# Rectification_filter.net
KiCad netlist of a schematic drawn in Altium Designer
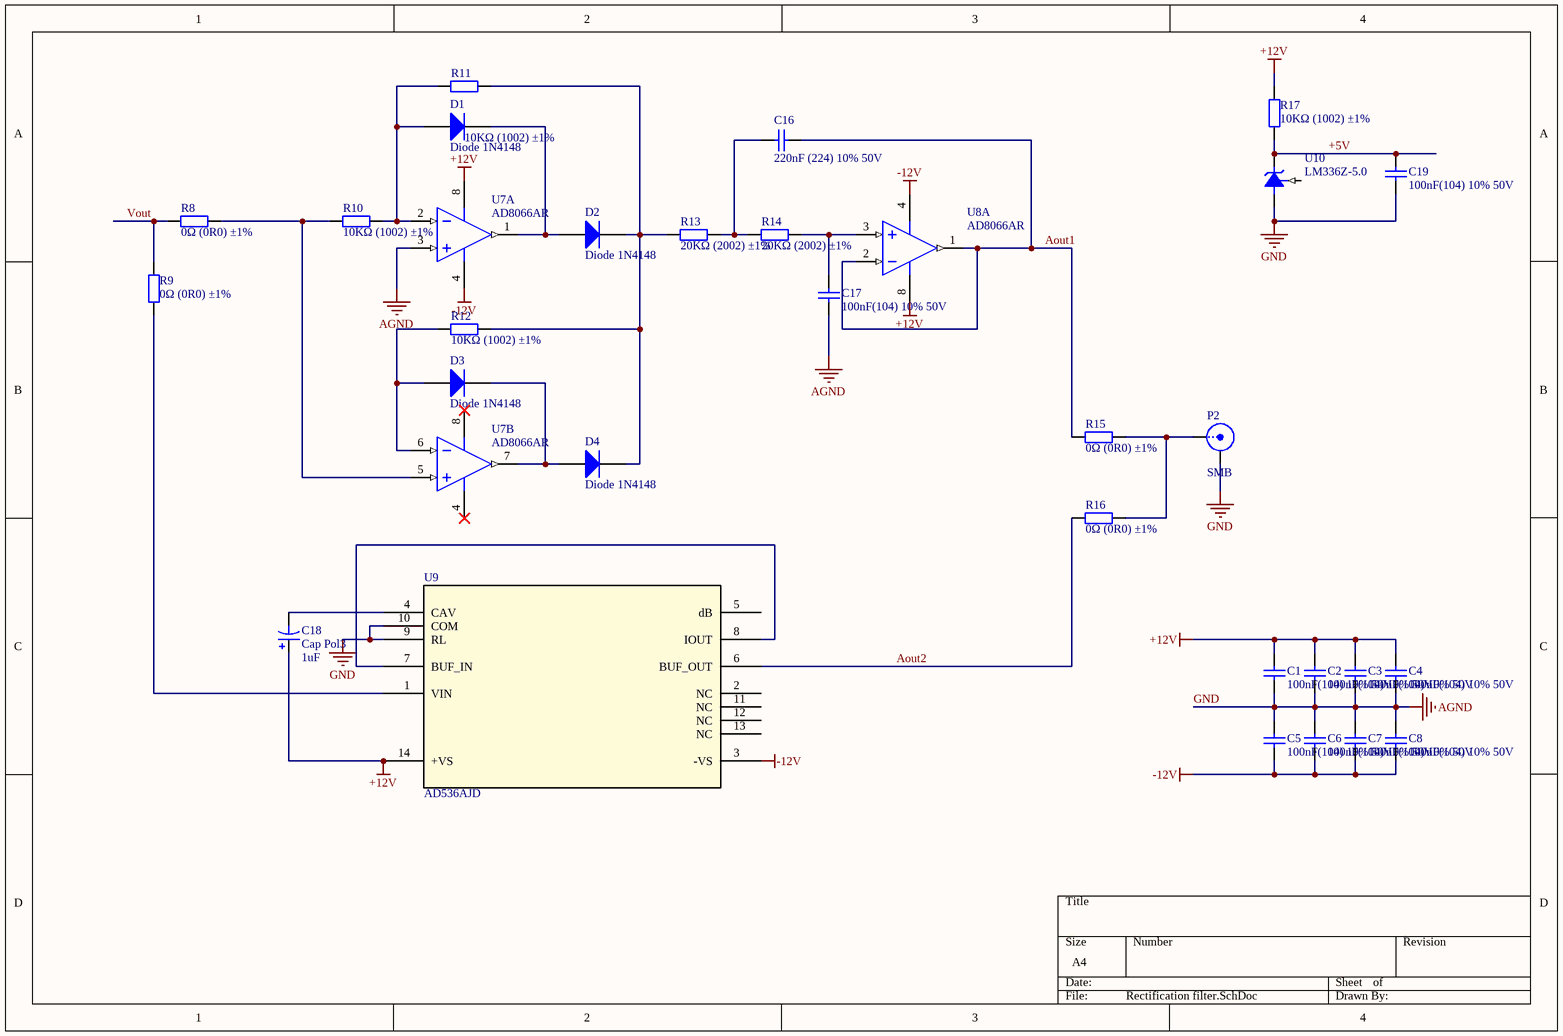
[diagram p0: Rectification filter.SchDoc]

(export (version "E")
  (design (tool "Eeschema 10.0.6"))
  (components
    (comp (ref "C1")
      (value "100nF(104) 10% 50V")
      (footprint "LC-0805_C")
      (description "贴片电容")
      (libsource (lib "Miscellaneous Devices LC") (part "0805 100nF(104) 10% 50V"))
    )
    (comp (ref "C2")
      (value "100nF(104) 10% 50V")
      (footprint "LC-0805_C")
      (description "贴片电容")
      (libsource (lib "Miscellaneous Devices LC") (part "0805 100nF(104) 10% 50V"))
    )
    (comp (ref "C3")
      (value "100nF(104) 10% 50V")
      (footprint "LC-0805_C")
      (description "贴片电容")
      (libsource (lib "Miscellaneous Devices LC") (part "0805 100nF(104) 10% 50V"))
    )
    (comp (ref "C4")
      (value "100nF(104) 10% 50V")
      (footprint "LC-0805_C")
      (description "贴片电容")
      (libsource (lib "Miscellaneous Devices LC") (part "0805 100nF(104) 10% 50V"))
    )
    (comp (ref "C5")
      (value "100nF(104) 10% 50V")
      (footprint "LC-0805_C")
      (description "贴片电容")
      (libsource (lib "Miscellaneous Devices LC") (part "0805 100nF(104) 10% 50V"))
    )
    (comp (ref "C6")
      (value "100nF(104) 10% 50V")
      (footprint "LC-0805_C")
      (description "贴片电容")
      (libsource (lib "Miscellaneous Devices LC") (part "0805 100nF(104) 10% 50V"))
    )
    (comp (ref "C7")
      (value "100nF(104) 10% 50V")
      (footprint "LC-0805_C")
      (description "贴片电容")
      (libsource (lib "Miscellaneous Devices LC") (part "0805 100nF(104) 10% 50V"))
    )
    (comp (ref "C8")
      (value "100nF(104) 10% 50V")
      (footprint "LC-0805_C")
      (description "贴片电容")
      (libsource (lib "Miscellaneous Devices LC") (part "0805 100nF(104) 10% 50V"))
    )
    (comp (ref "C16")
      (value "220nF (224) 10% 50V")
      (footprint "LC-0805_C")
      (description "贴片电容")
      (libsource (lib "Miscellaneous Devices LC") (part "0805 220nF (224) 10% 50V"))
    )
    (comp (ref "C17")
      (value "100nF(104) 10% 50V")
      (footprint "LC-0805_C")
      (description "贴片电容")
      (libsource (lib "Miscellaneous Devices LC") (part "0805 100nF(104) 10% 50V"))
    )
    (comp (ref "C18")
      (value "Cap Pol3")
      (footprint "C0805")
      (description "Polarized Capacitor (Surface Mount)")
      (fields (field (name "ALTIUM_VALUE") "1uF") (field (name "PUBLISHER") "Altium Limited"))
      (libsource (lib "Miscellaneous Devices") (part "Cap Pol3"))
    )
    (comp (ref "C19")
      (value "100nF(104) 10% 50V")
      (footprint "LC-0805_C")
      (description "贴片电容")
      (libsource (lib "Miscellaneous Devices LC") (part "0805 100nF(104) 10% 50V"))
    )
    (comp (ref "D1")
      (value "Diode 1N4148")
      (footprint "DO-35")
      (description "High Conductance Fast Diode")
      (fields (field (name "PUBLISHER") "Altium Limited"))
      (libsource (lib "Miscellaneous Devices") (part "Diode 1N4148"))
    )
    (comp (ref "D2")
      (value "Diode 1N4148")
      (footprint "DO-35")
      (description "High Conductance Fast Diode")
      (fields (field (name "PUBLISHER") "Altium Limited"))
      (libsource (lib "Miscellaneous Devices") (part "Diode 1N4148"))
    )
    (comp (ref "D3")
      (value "Diode 1N4148")
      (footprint "DO-35")
      (description "High Conductance Fast Diode")
      (fields (field (name "PUBLISHER") "Altium Limited"))
      (libsource (lib "Miscellaneous Devices") (part "Diode 1N4148"))
    )
    (comp (ref "D4")
      (value "Diode 1N4148")
      (footprint "DO-35")
      (description "High Conductance Fast Diode")
      (fields (field (name "PUBLISHER") "Altium Limited"))
      (libsource (lib "Miscellaneous Devices") (part "Diode 1N4148"))
    )
    (comp (ref "P2")
      (value "SMB")
      (footprint "SMB_V-RJ45")
      (description "SMB Straight Connector")
      (fields (field (name "PUBLISHER") "Altium Limited"))
      (libsource (lib "Miscellaneous Connectors") (part "SMB"))
    )
    (comp (ref "R8")
      (value "0Ω (0R0) ±1%")
      (footprint "LC-0805_R")
      (description "贴片电阻")
      (libsource (lib "Miscellaneous Devices LC") (part "0805 0Ω (0R0) 1%"))
    )
    (comp (ref "R9")
      (value "0Ω (0R0) ±1%")
      (footprint "LC-0805_R")
      (description "贴片电阻")
      (libsource (lib "") (part "0805 0Ω (0R0) 1%_1"))
    )
    (comp (ref "R10")
      (value "10KΩ (1002) ±1%")
      (footprint "LC-0805_R")
      (description "贴片电阻")
      (libsource (lib "") (part "0805 10KΩ (1002) 1%_1"))
    )
    (comp (ref "R11")
      (value "10KΩ (1002) ±1%")
      (footprint "LC-0805_R")
      (description "贴片电阻")
      (libsource (lib "") (part "0805 10KΩ (1002) 1%_1"))
    )
    (comp (ref "R12")
      (value "10KΩ (1002) ±1%")
      (footprint "LC-0805_R")
      (description "贴片电阻")
      (libsource (lib "") (part "0805 10KΩ (1002) 1%_1"))
    )
    (comp (ref "R13")
      (value "20KΩ (2002) ±1%")
      (footprint "LC-0805_R")
      (description "贴片电阻")
      (libsource (lib "Miscellaneous Devices LC") (part "0805 20KΩ (2002) 1%"))
    )
    (comp (ref "R14")
      (value "20KΩ (2002) ±1%")
      (footprint "LC-0805_R")
      (description "贴片电阻")
      (libsource (lib "Miscellaneous Devices LC") (part "0805 20KΩ (2002) 1%"))
    )
    (comp (ref "R15")
      (value "0Ω (0R0) ±1%")
      (footprint "LC-0805_R")
      (description "贴片电阻")
      (libsource (lib "Miscellaneous Devices LC") (part "0805 0Ω (0R0) 1%"))
    )
    (comp (ref "R16")
      (value "0Ω (0R0) ±1%")
      (footprint "LC-0805_R")
      (description "贴片电阻")
      (libsource (lib "Miscellaneous Devices LC") (part "0805 0Ω (0R0) 1%"))
    )
    (comp (ref "R17")
      (value "10KΩ (1002) ±1%")
      (footprint "LC-0805_R")
      (description "贴片电阻")
      (libsource (lib "Miscellaneous Devices LC") (part "0805 10KΩ (1002) 1%"))
    )
    (comp (ref "U7")
      (value "AD8066AR")
      (footprint "ADI-R-8_N")
      (fields (field (name "GENERIC PART NUMBER") "AD8066") (field (name "MANUFACTURER") "Analog Devices"))
      (libsource (lib "Analog Devices Operational Amplifiers") (part "AD8066AR"))
    )
    (comp (ref "U8")
      (value "AD8066AR")
      (footprint "ADI-R-8_N")
      (fields (field (name "GENERIC PART NUMBER") "AD8066") (field (name "MANUFACTURER") "Analog Devices"))
      (libsource (lib "Analog Devices Operational Amplifiers") (part "AD8066AR"))
    )
    (comp (ref "U9")
      (value "AD536AJD")
      (footprint "D_14")
      (description "Imported")
      (libsource (lib "AD536AJD") (part "AD536AJD"))
    )
    (comp (ref "U10")
      (value "LM336Z-5.0")
      (footprint "TO-92")
      (description "5.0V Reference Diode, 3-pin TO-92")
      (fields
        (field (name "MANUFACTURER") "National Semiconductor")
        (field (name "PUBLISHER") "Altium Limited")
      )
      (libsource (lib "NSC Voltage Reference") (part "LM336Z-5.0"))
    )
  )
  (nets
    (net (code "1") (name "+12V") (class "Default")
      (node (ref "C1") (pin "2") (pinfunction "2_2") (pintype "passive"))
      (node (ref "C18") (pin "1") (pinfunction "1_1") (pintype "passive"))
      (node (ref "C2") (pin "2") (pinfunction "2_2") (pintype "passive"))
      (node (ref "C3") (pin "2") (pinfunction "2_2") (pintype "passive"))
      (node (ref "C4") (pin "2") (pinfunction "2_2") (pintype "passive"))
      (node (ref "R17") (pin "2") (pinfunction "2_2") (pintype "passive"))
      (node (ref "U7") (pin "8") (pinfunction "+VS_8") (pintype "power_in"))
      (node (ref "U8") (pin "8") (pinfunction "+VS_8") (pintype "power_in"))
      (node (ref "U9") (pin "14") (pinfunction "+VS_14") (pintype "power_in"))
    )
    (net (code "2") (name "-12V") (class "Default")
      (node (ref "C5") (pin "1") (pinfunction "1_1") (pintype "passive"))
      (node (ref "C6") (pin "1") (pinfunction "1_1") (pintype "passive"))
      (node (ref "C7") (pin "1") (pinfunction "1_1") (pintype "passive"))
      (node (ref "C8") (pin "1") (pinfunction "1_1") (pintype "passive"))
      (node (ref "U7") (pin "4") (pinfunction "-VS_4") (pintype "power_in"))
      (node (ref "U8") (pin "4") (pinfunction "-VS_4") (pintype "power_in"))
      (node (ref "U9") (pin "3") (pinfunction "-VS_3") (pintype "power_in"))
    )
    (net (code "3") (name "/+5V") (class "Default")
      (node (ref "C19") (pin "2") (pinfunction "2_2") (pintype "passive"))
      (node (ref "R17") (pin "1") (pinfunction "1_1") (pintype "passive"))
      (node (ref "U10") (pin "2") (pinfunction "+V_2") (pintype "passive"))
    )
    (net (code "4") (name "/Aout1") (class "Default")
      (node (ref "C16") (pin "2") (pinfunction "2_2") (pintype "passive"))
      (node (ref "R15") (pin "1") (pinfunction "1_1") (pintype "passive"))
      (node (ref "U8") (pin "1") (pinfunction "VOUT_1_1") (pintype "output"))
      (node (ref "U8") (pin "2") (pinfunction "-IN_1_2") (pintype "input"))
    )
    (net (code "5") (name "/Aout2") (class "Default")
      (node (ref "R16") (pin "1") (pinfunction "1_1") (pintype "passive"))
      (node (ref "U9") (pin "6") (pinfunction "BUF_OUT_6") (pintype "passive"))
    )
    (net (code "6") (name "/Vout") (class "Default")
      (node (ref "R8") (pin "1") (pinfunction "1_1") (pintype "passive"))
      (node (ref "R9") (pin "2") (pinfunction "2_2") (pintype "passive"))
    )
    (net (code "7") (name "AGND") (class "Default")
      (node (ref "C1") (pin "1") (pinfunction "1_1") (pintype "passive"))
      (node (ref "C17") (pin "1") (pinfunction "1_1") (pintype "passive"))
      (node (ref "C19") (pin "1") (pinfunction "1_1") (pintype "passive"))
      (node (ref "C2") (pin "1") (pinfunction "1_1") (pintype "passive"))
      (node (ref "C3") (pin "1") (pinfunction "1_1") (pintype "passive"))
      (node (ref "C4") (pin "1") (pinfunction "1_1") (pintype "passive"))
      (node (ref "C5") (pin "2") (pinfunction "2_2") (pintype "passive"))
      (node (ref "C6") (pin "2") (pinfunction "2_2") (pintype "passive"))
      (node (ref "C7") (pin "2") (pinfunction "2_2") (pintype "passive"))
      (node (ref "C8") (pin "2") (pinfunction "2_2") (pintype "passive"))
      (node (ref "P2") (pin "2") (pinfunction "Y_2") (pintype "passive"))
      (node (ref "U10") (pin "3") (pinfunction "-V_3") (pintype "passive"))
      (node (ref "U7") (pin "3") (pinfunction "+IN_1_3") (pintype "input"))
      (node (ref "U9") (pin "10") (pinfunction "COM_10") (pintype "passive"))
      (node (ref "U9") (pin "9") (pinfunction "RL_9") (pintype "passive"))
    )
    (net (code "8") (name "Net-(C16-Pad1)") (class "Default")
      (node (ref "C16") (pin "1") (pinfunction "1_1") (pintype "passive"))
      (node (ref "R13") (pin "2") (pinfunction "2_2") (pintype "passive"))
      (node (ref "R14") (pin "1") (pinfunction "1_1") (pintype "passive"))
    )
    (net (code "9") (name "Net-(D1-A)") (class "Default")
      (node (ref "D1") (pin "1") (pinfunction "A_1") (pintype "passive"))
      (node (ref "R10") (pin "2") (pinfunction "2_2") (pintype "passive"))
      (node (ref "R11") (pin "1") (pinfunction "1_1") (pintype "passive"))
      (node (ref "U7") (pin "2") (pinfunction "-IN_1_2") (pintype "input"))
    )
    (net (code "10") (name "Net-(D1-K)") (class "Default")
      (node (ref "D1") (pin "2") (pinfunction "K_2") (pintype "passive"))
      (node (ref "D2") (pin "1") (pinfunction "A_1") (pintype "passive"))
      (node (ref "U7") (pin "1") (pinfunction "VOUT_1_1") (pintype "output"))
    )
    (net (code "11") (name "Net-(D2-K)") (class "Default")
      (node (ref "D2") (pin "2") (pinfunction "K_2") (pintype "passive"))
      (node (ref "D4") (pin "2") (pinfunction "K_2") (pintype "passive"))
      (node (ref "R11") (pin "2") (pinfunction "2_2") (pintype "passive"))
      (node (ref "R12") (pin "2") (pinfunction "2_2") (pintype "passive"))
      (node (ref "R13") (pin "1") (pinfunction "1_1") (pintype "passive"))
    )
    (net (code "12") (name "Net-(D3-A)") (class "Default")
      (node (ref "D3") (pin "1") (pinfunction "A_1") (pintype "passive"))
      (node (ref "R12") (pin "1") (pinfunction "1_1") (pintype "passive"))
      (node (ref "U7") (pin "6") (pinfunction "-IN_2_6") (pintype "input"))
    )
    (net (code "13") (name "Net-(D3-K)") (class "Default")
      (node (ref "D3") (pin "2") (pinfunction "K_2") (pintype "passive"))
      (node (ref "D4") (pin "1") (pinfunction "A_1") (pintype "passive"))
      (node (ref "U7") (pin "7") (pinfunction "VOUT_2_7") (pintype "output"))
    )
    (net (code "14") (name "Net-(P2-X)") (class "Default")
      (node (ref "P2") (pin "1") (pinfunction "X_1") (pintype "passive"))
      (node (ref "R15") (pin "2") (pinfunction "2_2") (pintype "passive"))
      (node (ref "R16") (pin "2") (pinfunction "2_2") (pintype "passive"))
    )
    (net (code "15") (name "Net-(U7B-+IN_2)") (class "Default")
      (node (ref "R10") (pin "1") (pinfunction "1_1") (pintype "passive"))
      (node (ref "R8") (pin "2") (pinfunction "2_2") (pintype "passive"))
      (node (ref "U7") (pin "5") (pinfunction "+IN_2_5") (pintype "input"))
    )
    (net (code "16") (name "Net-(U8A-+IN_1)") (class "Default")
      (node (ref "C17") (pin "2") (pinfunction "2_2") (pintype "passive"))
      (node (ref "R14") (pin "2") (pinfunction "2_2") (pintype "passive"))
      (node (ref "U8") (pin "3") (pinfunction "+IN_1_3") (pintype "input"))
    )
    (net (code "17") (name "Net-(U9-BUF_IN)") (class "Default")
      (node (ref "U9") (pin "7") (pinfunction "BUF_IN_7") (pintype "passive"))
      (node (ref "U9") (pin "8") (pinfunction "IOUT_8") (pintype "passive"))
    )
    (net (code "18") (name "Net-(U9-CAV)") (class "Default")
      (node (ref "C18") (pin "2") (pinfunction "2_2") (pintype "passive"))
      (node (ref "U9") (pin "4") (pinfunction "CAV_4") (pintype "passive"))
    )
    (net (code "19") (name "Net-(U9-VIN)") (class "Default")
      (node (ref "R9") (pin "1") (pinfunction "1_1") (pintype "passive"))
      (node (ref "U9") (pin "1") (pinfunction "VIN_1") (pintype "passive"))
    )
    (net (code "20") (name "unconnected-(U7B-+VS-Pad8)") (class "Default")
      (node (ref "U7") (pin "8") (pinfunction "+VS_8") (pintype "power_in+no_connect"))
    )
    (net (code "21") (name "unconnected-(U7B--VS-Pad4)") (class "Default")
      (node (ref "U7") (pin "4") (pinfunction "-VS_4") (pintype "power_in+no_connect"))
    )
    (net (code "22") (name "unconnected-(U9-NC-Pad2)") (class "Default")
      (node (ref "U9") (pin "2") (pinfunction "NC_2") (pintype "passive"))
    )
    (net (code "23") (name "unconnected-(U9-NC-Pad11)") (class "Default")
      (node (ref "U9") (pin "11") (pinfunction "NC_11") (pintype "passive"))
    )
    (net (code "24") (name "unconnected-(U9-NC-Pad12)") (class "Default")
      (node (ref "U9") (pin "12") (pinfunction "NC_12") (pintype "passive"))
    )
    (net (code "25") (name "unconnected-(U9-NC-Pad13)") (class "Default")
      (node (ref "U9") (pin "13") (pinfunction "NC_13") (pintype "passive"))
    )
    (net (code "26") (name "unconnected-(U9-dB-Pad5)") (class "Default")
      (node (ref "U9") (pin "5") (pinfunction "dB_5") (pintype "passive"))
    )
    (net (code "27") (name "unconnected-(U10-ADJ-Pad1)") (class "Default")
      (node (ref "U10") (pin "1") (pinfunction "ADJ_1") (pintype "input"))
    )
  )
)
